# Ethernet_3.net
KiCad netlist of a schematic drawn in Altium Designer
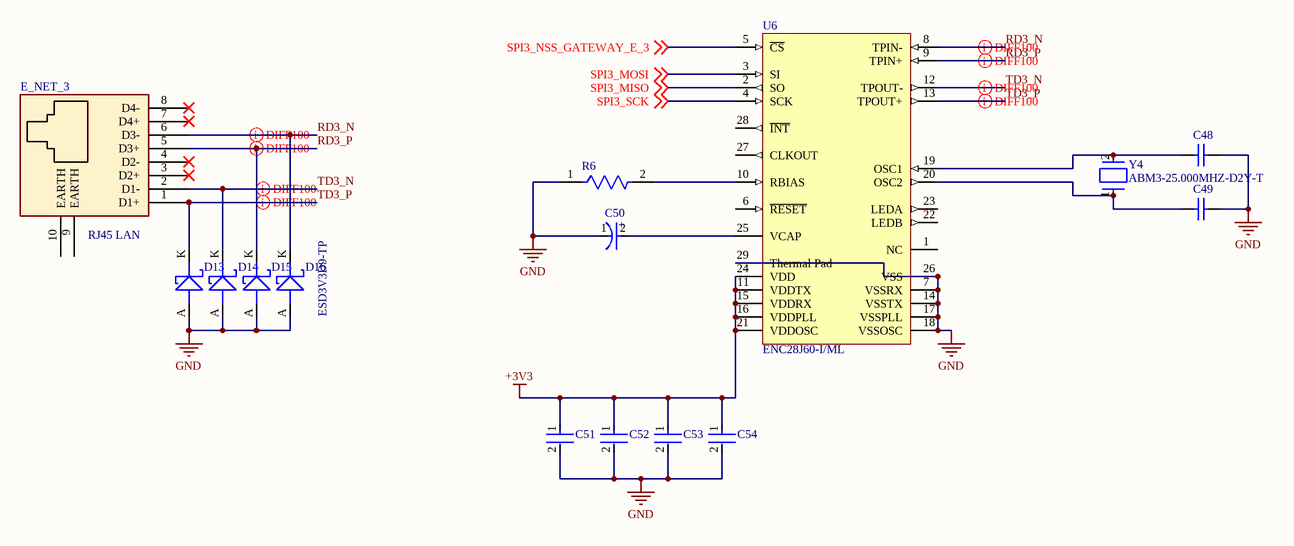
[diagram p0: Ethernet_3.SchDoc]

(export (version "E")
  (design (tool "Eeschema 10.0.6"))
  (components
    (comp (ref "C48")
      (value "CC0603JRNPO9BN180")
      (footprint "CAPC1608X90X40LL10T20")
      (description "Chip Capacitor, 18 pF, +/- 5%, 50 V, -55 to 125 degC, 0603 (1608 Metric), RoHS, Tape and Reel")
      (fields (field (name "TOLERANCE") "1%"))
      (libsource (lib "Altium Content Vault") (part "CAP-NP-2"))
    )
    (comp (ref "C49")
      (value "CC0603JRNPO9BN180")
      (footprint "CAPC1608X90X40LL10T20")
      (description "Chip Capacitor, 18 pF, +/- 5%, 50 V, -55 to 125 degC, 0603 (1608 Metric), RoHS, Tape and Reel")
      (fields (field (name "TOLERANCE") "1%"))
      (libsource (lib "Altium Content Vault") (part "CAP-NP-2"))
    )
    (comp (ref "C50")
      (value "593D106X9016A2TE3")
      (footprint "FP-593DA-MFG")
      (fields (field (name "TOLERANCE") "10%") (field (name "VOLTAGE") "16V"))
      (libsource (lib "Altium Content Vault") (part "a00bbbee19879c290e62620ae7e47b1"))
    )
    (comp (ref "C51")
      (value "C0402C104K8RACTU")
      (footprint "FP-C0402-BB-MFG")
      (description "CAP CER 0.1UF 10V X7R 0402")
      (fields
        (field (name "OCTOPART") "https://octopart.com/c0402c104k8ractu-kemet-106349")
        (field (name "TOLERANCE") "0.1")
      )
      (libsource (lib "Altium Content Vault") (part "b4654b650e69147ec39a6b967a45e02"))
    )
    (comp (ref "C52")
      (value "C0402C104K8RACTU")
      (footprint "FP-C0402-BB-MFG")
      (description "CAP CER 0.1UF 10V X7R 0402")
      (fields
        (field (name "OCTOPART") "https://octopart.com/c0402c104k8ractu-kemet-106349")
        (field (name "TOLERANCE") "0.1")
      )
      (libsource (lib "Altium Content Vault") (part "b4654b650e69147ec39a6b967a45e02"))
    )
    (comp (ref "C53")
      (value "C0402C104K8RACTU")
      (footprint "FP-C0402-BB-MFG")
      (description "CAP CER 0.1UF 10V X7R 0402")
      (fields
        (field (name "OCTOPART") "https://octopart.com/c0402c104k8ractu-kemet-106349")
        (field (name "TOLERANCE") "0.1")
      )
      (libsource (lib "Altium Content Vault") (part "b4654b650e69147ec39a6b967a45e02"))
    )
    (comp (ref "C54")
      (value "C0402C104K8RACTU")
      (footprint "FP-C0402-BB-MFG")
      (description "CAP CER 0.1UF 10V X7R 0402")
      (fields
        (field (name "OCTOPART") "https://octopart.com/c0402c104k8ractu-kemet-106349")
        (field (name "TOLERANCE") "0.1")
      )
      (libsource (lib "Altium Content Vault") (part "b4654b650e69147ec39a6b967a45e02"))
    )
    (comp (ref "D13")
      (value "ESD3V3D9-TP")
      (footprint "DIO_SOD-923")
      (description "8.8V Clamp 5A (8/20µs) Ipp Tvs Diode Surface Mount SOD-923")
      (fields (field (name "MANUFACTURER") "Micro Commercial Co"))
      (libsource (lib "ESTEEMPCBLIB") (part "DIO-T_3.3V-8.8V-SOD923"))
    )
    (comp (ref "D14")
      (value "ESD3V3D9-TP")
      (footprint "DIO_SOD-923")
      (description "8.8V Clamp 5A (8/20µs) Ipp Tvs Diode Surface Mount SOD-923")
      (fields (field (name "MANUFACTURER") "Micro Commercial Co"))
      (libsource (lib "ESTEEMPCBLIB") (part "DIO-T_3.3V-8.8V-SOD923"))
    )
    (comp (ref "D15")
      (value "ESD3V3D9-TP")
      (footprint "DIO_SOD-923")
      (description "8.8V Clamp 5A (8/20µs) Ipp Tvs Diode Surface Mount SOD-923")
      (fields (field (name "MANUFACTURER") "Micro Commercial Co"))
      (libsource (lib "ESTEEMPCBLIB") (part "DIO-T_3.3V-8.8V-SOD923"))
    )
    (comp (ref "D16")
      (value "ESD3V3D9-TP")
      (footprint "DIO_SOD-923")
      (description "8.8V Clamp 5A (8/20µs) Ipp Tvs Diode Surface Mount SOD-923")
      (fields (field (name "MANUFACTURER") "Micro Commercial Co"))
      (libsource (lib "ESTEEMPCBLIB") (part "DIO-T_3.3V-8.8V-SOD923"))
    )
    (comp (ref "E_NET_3")
      (value "RJ45 LAN")
      (footprint "CON10_P106_RJ45_TH_ST")
      (description "8 Pins, 2 Row 2.54mm Pitch, right angle Connector, male")
      (fields
        (field (name "MANUFACTURER") "Assmann")
        (field (name "MANUFACTURER PART NUMBER") "A-2004-2-4-LPS-N-R")
      )
      (libsource (lib "ESTEEMPCBLIB") (part "CON-SKT-RJ_8C8P-RA-TH"))
    )
    (comp (ref "R6")
      (value "ERJ-2RKF2001X")
      (footprint "FP-ERJ2RK-MFG")
      (description "RES SMD 2K OHM 1% 1/10W 0402")
      (fields (field (name "TOLERANCE") "1%"))
      (libsource (lib "Altium Content Vault") (part "1029c3af85768c4190bb7ad29bc67b5"))
    )
    (comp (ref "U6")
      (value "ENC28J60-I/ML")
      (footprint "QFN-ML28_M")
      (description "Stand-Alone Ethernet Controller with SPI Interface, 28-Pin QFN, Industrial Temperature")
      (libsource (lib "Altium Content Vault") (part "COM-ENET-ENC28J60-29"))
    )
    (comp (ref "Y4")
      (value "ABM3-25.000MHZ-D2Y-T")
      (footprint "FP-ABM3-MFG")
      (description "Crystal 25MHz ±20ppm 18pF SMD-2 5mm x 3.2mm")
      (fields (field (name "TOLERANCE") "20ppm"))
      (libsource (lib "Altium Content Vault") (part "c23a69dc6c9e2f18f2079038eb95dd1"))
    )
  )
  (nets
    (net (code "1") (name "+3V3") (class "Default")
      (node (ref "C51") (pin "1") (pinfunction "1_1") (pintype "passive"))
      (node (ref "C52") (pin "1") (pinfunction "1_1") (pintype "passive"))
      (node (ref "C53") (pin "1") (pinfunction "1_1") (pintype "passive"))
      (node (ref "C54") (pin "1") (pinfunction "1_1") (pintype "passive"))
      (node (ref "U6") (pin "11") (pinfunction "VDDTX_11") (pintype "power_in"))
      (node (ref "U6") (pin "15") (pinfunction "VDDRX_15") (pintype "power_in"))
      (node (ref "U6") (pin "16") (pinfunction "VDDPLL_16") (pintype "power_in"))
      (node (ref "U6") (pin "21") (pinfunction "VDDOSC_21") (pintype "power_in"))
      (node (ref "U6") (pin "24") (pinfunction "VDD_24") (pintype "power_in"))
    )
    (net (code "2") (name "/RD3_N") (class "Default")
      (node (ref "D16") (pin "K") (pinfunction "K_K") (pintype "passive"))
      (node (ref "E_NET_3") (pin "6") (pinfunction "D3-_6") (pintype "passive"))
      (node (ref "U6") (pin "8") (pinfunction "TPIN-_8") (pintype "input"))
    )
    (net (code "3") (name "/RD3_P") (class "Default")
      (node (ref "D15") (pin "K") (pinfunction "K_K") (pintype "passive"))
      (node (ref "E_NET_3") (pin "5") (pinfunction "D3+_5") (pintype "passive"))
      (node (ref "U6") (pin "9") (pinfunction "TPIN+_9") (pintype "input"))
    )
    (net (code "4") (name "/TD3_N") (class "Default")
      (node (ref "D14") (pin "K") (pinfunction "K_K") (pintype "passive"))
      (node (ref "E_NET_3") (pin "2") (pinfunction "D1-_2") (pintype "passive"))
      (node (ref "U6") (pin "12") (pinfunction "TPOUT-_12") (pintype "output"))
    )
    (net (code "5") (name "/TD3_P") (class "Default")
      (node (ref "D13") (pin "K") (pinfunction "K_K") (pintype "passive"))
      (node (ref "E_NET_3") (pin "1") (pinfunction "D1+_1") (pintype "passive"))
      (node (ref "U6") (pin "13") (pinfunction "TPOUT+_13") (pintype "output"))
    )
    (net (code "6") (name "GND") (class "Default")
      (node (ref "C48") (pin "1") (pinfunction "1_1") (pintype "passive"))
      (node (ref "C49") (pin "1") (pinfunction "1_1") (pintype "passive"))
      (node (ref "C50") (pin "1") (pinfunction "C_1") (pintype "passive"))
      (node (ref "C51") (pin "2") (pinfunction "2_2") (pintype "passive"))
      (node (ref "C52") (pin "2") (pinfunction "2_2") (pintype "passive"))
      (node (ref "C53") (pin "2") (pinfunction "2_2") (pintype "passive"))
      (node (ref "C54") (pin "2") (pinfunction "2_2") (pintype "passive"))
      (node (ref "D13") (pin "A") (pinfunction "A_A") (pintype "passive"))
      (node (ref "D14") (pin "A") (pinfunction "A_A") (pintype "passive"))
      (node (ref "D15") (pin "A") (pinfunction "A_A") (pintype "passive"))
      (node (ref "D16") (pin "A") (pinfunction "A_A") (pintype "passive"))
      (node (ref "R6") (pin "1") (pinfunction "1_1") (pintype "passive"))
      (node (ref "U6") (pin "14") (pinfunction "VSSTX_14") (pintype "power_in"))
      (node (ref "U6") (pin "17") (pinfunction "VSSPLL_17") (pintype "power_in"))
      (node (ref "U6") (pin "18") (pinfunction "VSSOSC_18") (pintype "power_in"))
      (node (ref "U6") (pin "26") (pinfunction "VSS_26") (pintype "power_in"))
      (node (ref "U6") (pin "29") (pinfunction "Thermal_Pad_29") (pintype "passive"))
      (node (ref "U6") (pin "7") (pinfunction "VSSRX_7") (pintype "power_in"))
    )
    (net (code "7") (name "Net-(C50-A)") (class "Default")
      (node (ref "C50") (pin "2") (pinfunction "A_2") (pintype "passive"))
      (node (ref "U6") (pin "25") (pinfunction "VCAP_25") (pintype "power_in"))
    )
    (net (code "8") (name "Net-(U6-OSC1)") (class "Default")
      (node (ref "C48") (pin "2") (pinfunction "2_2") (pintype "passive"))
      (node (ref "U6") (pin "19") (pinfunction "OSC1_19") (pintype "input"))
      (node (ref "Y4") (pin "2") (pinfunction "2_2") (pintype "passive"))
    )
    (net (code "9") (name "Net-(U6-OSC2)") (class "Default")
      (node (ref "C49") (pin "2") (pinfunction "2_2") (pintype "passive"))
      (node (ref "U6") (pin "20") (pinfunction "OSC2_20") (pintype "output"))
      (node (ref "Y4") (pin "1") (pinfunction "1_1") (pintype "passive"))
    )
    (net (code "10") (name "Net-(U6-RBIAS)") (class "Default")
      (node (ref "R6") (pin "2") (pinfunction "2_2") (pintype "passive"))
      (node (ref "U6") (pin "10") (pinfunction "RBIAS_10") (pintype "input"))
    )
    (net (code "11") (name "SPI3_MISO") (class "Default")
      (node (ref "U6") (pin "2") (pinfunction "SO_2") (pintype "output"))
    )
    (net (code "12") (name "SPI3_MOSI") (class "Default")
      (node (ref "U6") (pin "3") (pinfunction "SI_3") (pintype "input"))
    )
    (net (code "13") (name "SPI3_NSS_GATEWAY_E_3") (class "Default")
      (node (ref "U6") (pin "5") (pinfunction "~{CS}_5") (pintype "input"))
    )
    (net (code "14") (name "SPI3_SCK") (class "Default")
      (node (ref "U6") (pin "4") (pinfunction "SCK_4") (pintype "input"))
    )
    (net (code "15") (name "unconnected-(E_NET_3-D2+-Pad3)") (class "Default")
      (node (ref "E_NET_3") (pin "3") (pinfunction "D2+_3") (pintype "passive+no_connect"))
    )
    (net (code "16") (name "unconnected-(E_NET_3-D2--Pad4)") (class "Default")
      (node (ref "E_NET_3") (pin "4") (pinfunction "D2-_4") (pintype "passive+no_connect"))
    )
    (net (code "17") (name "unconnected-(E_NET_3-D4+-Pad7)") (class "Default")
      (node (ref "E_NET_3") (pin "7") (pinfunction "D4+_7") (pintype "passive+no_connect"))
    )
    (net (code "18") (name "unconnected-(E_NET_3-D4--Pad8)") (class "Default")
      (node (ref "E_NET_3") (pin "8") (pinfunction "D4-_8") (pintype "passive+no_connect"))
    )
    (net (code "19") (name "unconnected-(E_NET_3-EARTH-Pad9)") (class "Default")
      (node (ref "E_NET_3") (pin "9") (pinfunction "EARTH_9") (pintype "passive"))
    )
    (net (code "20") (name "unconnected-(E_NET_3-EARTH-Pad10)") (class "Default")
      (node (ref "E_NET_3") (pin "10") (pinfunction "EARTH_10") (pintype "passive"))
    )
    (net (code "21") (name "unconnected-(U6-CLKOUT-Pad27)") (class "Default")
      (node (ref "U6") (pin "27") (pinfunction "CLKOUT_27") (pintype "output"))
    )
    (net (code "22") (name "unconnected-(U6-LEDA-Pad23)") (class "Default")
      (node (ref "U6") (pin "23") (pinfunction "LEDA_23") (pintype "output"))
    )
    (net (code "23") (name "unconnected-(U6-LEDB-Pad22)") (class "Default")
      (node (ref "U6") (pin "22") (pinfunction "LEDB_22") (pintype "output"))
    )
    (net (code "24") (name "unconnected-(U6-NC-Pad1)") (class "Default")
      (node (ref "U6") (pin "1") (pinfunction "NC_1") (pintype "passive"))
    )
    (net (code "25") (name "unconnected-(U6-~{INT}-Pad28)") (class "Default")
      (node (ref "U6") (pin "28") (pinfunction "~{INT}_28") (pintype "output"))
    )
    (net (code "26") (name "unconnected-(U6-~{RESET}-Pad6)") (class "Default")
      (node (ref "U6") (pin "6") (pinfunction "~{RESET}_6") (pintype "input"))
    )
  )
)
